# Ver5_1.net
KiCad netlist of a schematic drawn in EAGLE
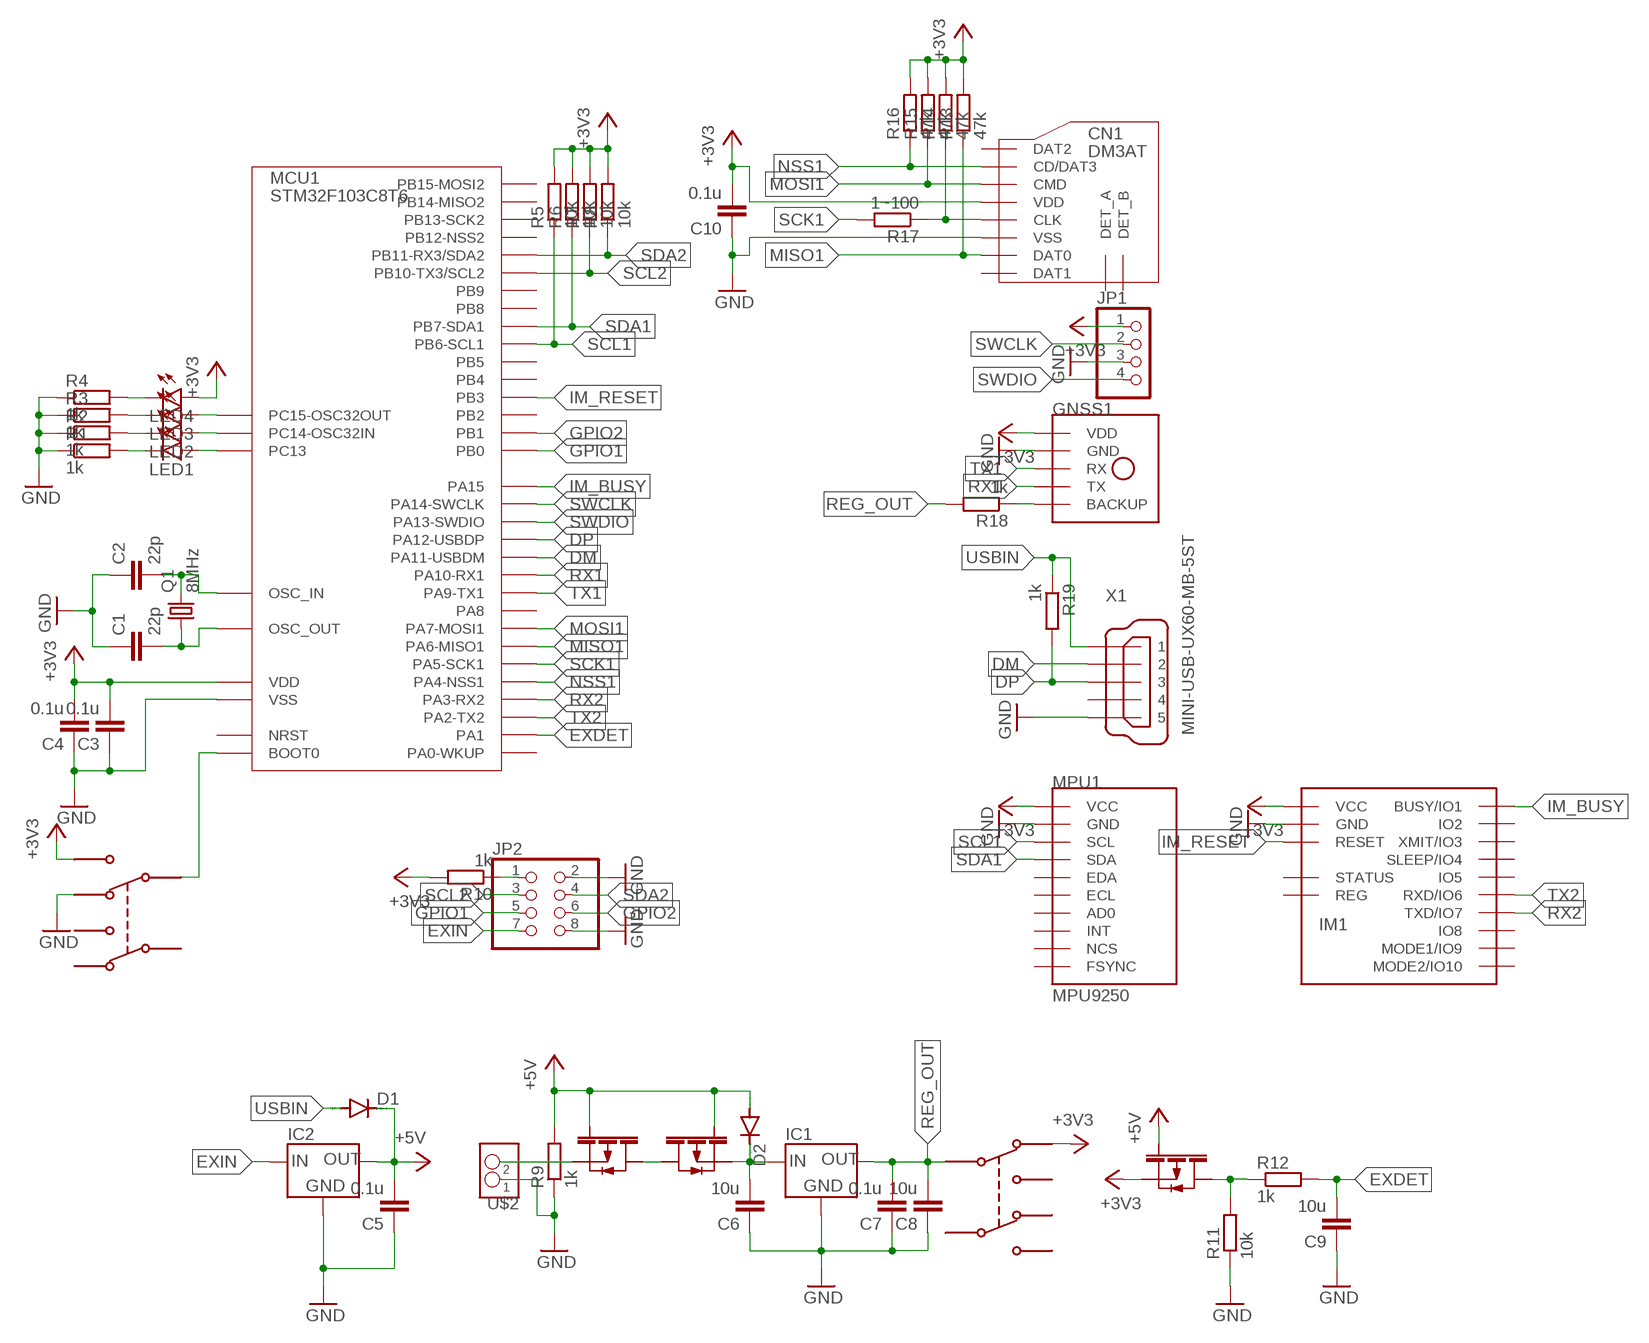
[diagram p0: schematic, sheet 1]

(export (version "E")
  (design (tool "Eeschema 10.0.6"))
  (components
    (comp (ref "C1")
      (value "22p")
      (footprint "eagle-import:C0805")
      (libsource (lib "eagle-import") (part "C-EUC0805"))
    )
    (comp (ref "C2")
      (value "22p")
      (footprint "eagle-import:C0805")
      (libsource (lib "eagle-import") (part "C-EUC0805"))
    )
    (comp (ref "C3")
      (value "0.1u")
      (footprint "eagle-import:C0805")
      (libsource (lib "eagle-import") (part "C-EUC0805"))
    )
    (comp (ref "C4")
      (value "0.1u")
      (footprint "eagle-import:C0805")
      (libsource (lib "eagle-import") (part "C-EUC0805"))
    )
    (comp (ref "C5")
      (value "0.1u")
      (footprint "eagle-import:C0805")
      (libsource (lib "eagle-import") (part "C-EUC0805"))
    )
    (comp (ref "C6")
      (value "10u")
      (footprint "eagle-import:C0805")
      (libsource (lib "eagle-import") (part "C-EUC0805"))
    )
    (comp (ref "C7")
      (value "0.1u")
      (footprint "eagle-import:C0805")
      (libsource (lib "eagle-import") (part "C-EUC0805"))
    )
    (comp (ref "C8")
      (value "10u")
      (footprint "eagle-import:C0805")
      (libsource (lib "eagle-import") (part "C-EUC0805"))
    )
    (comp (ref "C9")
      (value "10u")
      (footprint "eagle-import:C0805")
      (libsource (lib "eagle-import") (part "C-EUC0805"))
    )
    (comp (ref "C10")
      (value "0.1u")
      (footprint "eagle-import:C0805")
      (libsource (lib "eagle-import") (part "C-EUC0805"))
    )
    (comp (ref "CN1")
      (value "DM3AT")
      (footprint "eagle-import:DM3AT")
      (libsource (lib "eagle-import") (part "DM3AT"))
    )
    (comp (ref "D1")
      (value "DIODE-SOD123")
      (footprint "eagle-import:SOD123")
      (libsource (lib "eagle-import") (part "DIODE-SOD123"))
    )
    (comp (ref "D2")
      (value "DIODE-SOD123")
      (footprint "eagle-import:SOD123")
      (libsource (lib "eagle-import") (part "DIODE-SOD123"))
    )
    (comp (ref "FET1")
      (value "PCH")
      (footprint "eagle-import:SOT-23")
      (libsource (lib "eagle-import") (part "PCH"))
    )
    (comp (ref "FET2")
      (value "PCH")
      (footprint "eagle-import:SOT-23")
      (libsource (lib "eagle-import") (part "PCH"))
    )
    (comp (ref "FET3")
      (value "PCH")
      (footprint "eagle-import:SOT-23")
      (libsource (lib "eagle-import") (part "PCH"))
    )
    (comp (ref "GNSS1")
      (value "GYSFDMAXB")
      (footprint "eagle-import:GYSFDMAXB")
      (libsource (lib "eagle-import") (part "GYSFDMAXB"))
    )
    (comp (ref "IC1")
      (value "LT1117-3.3")
      (footprint "eagle-import:SOT-223")
      (libsource (lib "eagle-import") (part "LT1117-3.3"))
    )
    (comp (ref "IC2")
      (value "LT1117-5")
      (footprint "eagle-import:SOT-223")
      (libsource (lib "eagle-import") (part "LT1117-5"))
    )
    (comp (ref "IM1")
      (value "IM920C")
      (footprint "eagle-import:IM920C")
      (libsource (lib "eagle-import") (part "IM920C"))
    )
    (comp (ref "JP1")
      (value "PINHD-1X4/90")
      (footprint "eagle-import:1X04_90")
      (libsource (lib "eagle-import") (part "PINHD-1X4/90"))
    )
    (comp (ref "JP2")
      (value "PINHD-2X4")
      (footprint "eagle-import:2X04")
      (libsource (lib "eagle-import") (part "PINHD-2X4"))
    )
    (comp (ref "LED1")
      (value "LEDSML0805")
      (footprint "eagle-import:SML0805")
      (libsource (lib "eagle-import") (part "LEDSML0805"))
    )
    (comp (ref "LED2")
      (value "LEDSML0805")
      (footprint "eagle-import:SML0805")
      (libsource (lib "eagle-import") (part "LEDSML0805"))
    )
    (comp (ref "LED3")
      (value "LEDSML0805")
      (footprint "eagle-import:SML0805")
      (libsource (lib "eagle-import") (part "LEDSML0805"))
    )
    (comp (ref "LED4")
      (value "LEDSML0805")
      (footprint "eagle-import:SML0805")
      (libsource (lib "eagle-import") (part "LEDSML0805"))
    )
    (comp (ref "MCU1")
      (value "STM32F103C8T6")
      (footprint "eagle-import:LQFP48")
      (libsource (lib "eagle-import") (part "STM32F103C8T6"))
    )
    (comp (ref "MPU1")
      (value "MPU9250")
      (footprint "eagle-import:GY-9250")
      (libsource (lib "eagle-import") (part "MPU9250"))
    )
    (comp (ref "Q1")
      (value "8MHz")
      (footprint "eagle-import:HC49_S")
      (libsource (lib "eagle-import") (part "CRYSTALHC49S"))
    )
    (comp (ref "R1")
      (value "1k")
      (footprint "eagle-import:R0805")
      (libsource (lib "eagle-import") (part "R-EU_R0805"))
    )
    (comp (ref "R2")
      (value "1k")
      (footprint "eagle-import:R0805")
      (libsource (lib "eagle-import") (part "R-EU_R0805"))
    )
    (comp (ref "R3")
      (value "1k")
      (footprint "eagle-import:R0805")
      (libsource (lib "eagle-import") (part "R-EU_R0805"))
    )
    (comp (ref "R4")
      (value "1k")
      (footprint "eagle-import:R0805")
      (libsource (lib "eagle-import") (part "R-EU_R0805"))
    )
    (comp (ref "R5")
      (value "10k")
      (footprint "eagle-import:R0805")
      (libsource (lib "eagle-import") (part "R-EU_R0805"))
    )
    (comp (ref "R6")
      (value "10k")
      (footprint "eagle-import:R0805")
      (libsource (lib "eagle-import") (part "R-EU_R0805"))
    )
    (comp (ref "R7")
      (value "10k")
      (footprint "eagle-import:R0805")
      (libsource (lib "eagle-import") (part "R-EU_R0805"))
    )
    (comp (ref "R8")
      (value "10k")
      (footprint "eagle-import:R0805")
      (libsource (lib "eagle-import") (part "R-EU_R0805"))
    )
    (comp (ref "R9")
      (value "1k")
      (footprint "eagle-import:R0805")
      (libsource (lib "eagle-import") (part "R-EU_R0805"))
    )
    (comp (ref "R10")
      (value "1k")
      (footprint "eagle-import:R0805")
      (libsource (lib "eagle-import") (part "R-EU_R0805"))
    )
    (comp (ref "R11")
      (value "10k")
      (footprint "eagle-import:R0805")
      (libsource (lib "eagle-import") (part "R-EU_R0805"))
    )
    (comp (ref "R12")
      (value "1k")
      (footprint "eagle-import:R0805")
      (libsource (lib "eagle-import") (part "R-EU_R0805"))
    )
    (comp (ref "R13")
      (value "47k")
      (footprint "eagle-import:R0805")
      (libsource (lib "eagle-import") (part "R-EU_R0805"))
    )
    (comp (ref "R14")
      (value "47k")
      (footprint "eagle-import:R0805")
      (libsource (lib "eagle-import") (part "R-EU_R0805"))
    )
    (comp (ref "R15")
      (value "47k")
      (footprint "eagle-import:R0805")
      (libsource (lib "eagle-import") (part "R-EU_R0805"))
    )
    (comp (ref "R16")
      (value "47k")
      (footprint "eagle-import:R0805")
      (libsource (lib "eagle-import") (part "R-EU_R0805"))
    )
    (comp (ref "R17")
      (value "1~100")
      (footprint "eagle-import:R0805")
      (libsource (lib "eagle-import") (part "R-EU_R0805"))
    )
    (comp (ref "R18")
      (value "1k")
      (footprint "eagle-import:R0805")
      (libsource (lib "eagle-import") (part "R-EU_R0805"))
    )
    (comp (ref "R19")
      (value "1k")
      (footprint "eagle-import:R0805")
      (libsource (lib "eagle-import") (part "R-EU_R0805"))
    )
    (comp (ref "U$1")
      (value "MSS22D18")
      (footprint "eagle-import:MSS22D18")
      (libsource (lib "eagle-import") (part "MSS22D18"))
    )
    (comp (ref "U$2")
      (value "S2B-XH-A")
      (footprint "eagle-import:S2B-XH-A")
      (libsource (lib "eagle-import") (part "S2B-XH-A"))
    )
    (comp (ref "U$3")
      (value "MSS22D18")
      (footprint "eagle-import:MSS22D18")
      (libsource (lib "eagle-import") (part "MSS22D18"))
    )
    (comp (ref "X1")
      (value "MINI-USB-UX60-MB-5ST")
      (footprint "eagle-import:UX60-MB-5ST")
      (libsource (lib "eagle-import") (part "MINI-USB-UX60-MB-5ST"))
    )
  )
  (nets
    (net (code "1") (name "+3V3") (class "Default")
      (node (ref "C10") (pin "2") (pinfunction "2_2") (pintype "passive"))
      (node (ref "C3") (pin "2") (pinfunction "2_2") (pintype "passive"))
      (node (ref "C4") (pin "2") (pinfunction "2_2") (pintype "passive"))
      (node (ref "CN1") (pin "VDD") (pinfunction "VDD_VDD") (pintype "bidirectional"))
      (node (ref "FET3") (pin "P$2") (pinfunction "P$2_P$2") (pintype "bidirectional"))
      (node (ref "GNSS1") (pin "P$16") (pinfunction "VDD_P$16") (pintype "bidirectional"))
      (node (ref "IM1") (pin "$P17") (pinfunction "VCC_$P17") (pintype "bidirectional"))
      (node (ref "JP1") (pin "1") (pinfunction "1_1") (pintype "passive"))
      (node (ref "LED4") (pin "A") (pinfunction "A_A") (pintype "passive"))
      (node (ref "MCU1") (pin "1") (pinfunction "VDD_1") (pintype "bidirectional"))
      (node (ref "MCU1") (pin "24") (pinfunction "VDD_24") (pintype "bidirectional"))
      (node (ref "MCU1") (pin "36") (pinfunction "VDD_36") (pintype "bidirectional"))
      (node (ref "MCU1") (pin "48") (pinfunction "VDD_48") (pintype "bidirectional"))
      (node (ref "MCU1") (pin "9") (pinfunction "VDD_9") (pintype "bidirectional"))
      (node (ref "MPU1") (pin "P1") (pinfunction "VCC_P1") (pintype "bidirectional"))
      (node (ref "R10") (pin "2") (pinfunction "2_2") (pintype "passive"))
      (node (ref "R13") (pin "2") (pinfunction "2_2") (pintype "passive"))
      (node (ref "R14") (pin "2") (pinfunction "2_2") (pintype "passive"))
      (node (ref "R15") (pin "2") (pinfunction "2_2") (pintype "passive"))
      (node (ref "R16") (pin "2") (pinfunction "2_2") (pintype "passive"))
      (node (ref "R5") (pin "2") (pinfunction "2_2") (pintype "passive"))
      (node (ref "R6") (pin "2") (pinfunction "2_2") (pintype "passive"))
      (node (ref "R7") (pin "2") (pinfunction "2_2") (pintype "passive"))
      (node (ref "R8") (pin "2") (pinfunction "2_2") (pintype "passive"))
      (node (ref "U$1") (pin "P$0") (pinfunction "P$1_P$0") (pintype "bidirectional"))
      (node (ref "U$3") (pin "P$3") (pinfunction "P$6_P$3") (pintype "bidirectional"))
    )
    (net (code "2") (name "+5V") (class "Default")
      (node (ref "C5") (pin "2") (pinfunction "2_2") (pintype "passive"))
      (node (ref "D1") (pin "C") (pinfunction "C_C") (pintype "passive"))
      (node (ref "D2") (pin "A") (pinfunction "A_A") (pintype "passive"))
      (node (ref "FET1") (pin "P$1") (pinfunction "P$1_P$1") (pintype "bidirectional"))
      (node (ref "FET2") (pin "P$1") (pinfunction "P$1_P$1") (pintype "bidirectional"))
      (node (ref "FET3") (pin "P$1") (pinfunction "P$1_P$1") (pintype "bidirectional"))
      (node (ref "IC2") (pin "2") (pinfunction "OUT_2") (pintype "output"))
      (node (ref "R9") (pin "2") (pinfunction "2_2") (pintype "passive"))
    )
    (net (code "3") (name "DM") (class "Default")
      (node (ref "MCU1") (pin "32") (pinfunction "PA11-USBDM_32") (pintype "bidirectional"))
      (node (ref "X1") (pin "2") (pinfunction "2_2") (pintype "input"))
    )
    (net (code "4") (name "DP") (class "Default")
      (node (ref "MCU1") (pin "33") (pinfunction "PA12-USBDP_33") (pintype "bidirectional"))
      (node (ref "R19") (pin "2") (pinfunction "2_2") (pintype "passive"))
      (node (ref "X1") (pin "3") (pinfunction "3_3") (pintype "input"))
    )
    (net (code "5") (name "EXDET") (class "Default")
      (node (ref "C9") (pin "2") (pinfunction "2_2") (pintype "passive"))
      (node (ref "MCU1") (pin "11") (pinfunction "PA1_11") (pintype "bidirectional"))
      (node (ref "R12") (pin "2") (pinfunction "2_2") (pintype "passive"))
    )
    (net (code "6") (name "EXIN") (class "Default")
      (node (ref "IC2") (pin "3") (pinfunction "IN_3") (pintype "input"))
      (node (ref "JP2") (pin "7") (pinfunction "7_7") (pintype "passive"))
    )
    (net (code "7") (name "GND") (class "Default")
      (node (ref "C1") (pin "1") (pinfunction "1_1") (pintype "passive"))
      (node (ref "C10") (pin "1") (pinfunction "1_1") (pintype "passive"))
      (node (ref "C2") (pin "1") (pinfunction "1_1") (pintype "passive"))
      (node (ref "C3") (pin "1") (pinfunction "1_1") (pintype "passive"))
      (node (ref "C4") (pin "1") (pinfunction "1_1") (pintype "passive"))
      (node (ref "C5") (pin "1") (pinfunction "1_1") (pintype "passive"))
      (node (ref "C6") (pin "1") (pinfunction "1_1") (pintype "passive"))
      (node (ref "C7") (pin "1") (pinfunction "1_1") (pintype "passive"))
      (node (ref "C8") (pin "1") (pinfunction "1_1") (pintype "passive"))
      (node (ref "C9") (pin "1") (pinfunction "1_1") (pintype "passive"))
      (node (ref "CN1") (pin "VSS") (pinfunction "VSS_VSS") (pintype "bidirectional"))
      (node (ref "GNSS1") (pin "P$1") (pinfunction "GND_P$1") (pintype "bidirectional"))
      (node (ref "GNSS1") (pin "P$10") (pinfunction "GND_P$10") (pintype "bidirectional"))
      (node (ref "GNSS1") (pin "P$12") (pinfunction "GND_P$12") (pintype "bidirectional"))
      (node (ref "GNSS1") (pin "P$19") (pinfunction "GND_P$19") (pintype "bidirectional"))
      (node (ref "GNSS1") (pin "P$2") (pinfunction "GND_P$2") (pintype "bidirectional"))
      (node (ref "GNSS1") (pin "P$20") (pinfunction "GND_P$20") (pintype "bidirectional"))
      (node (ref "GNSS1") (pin "P$7") (pinfunction "GND_P$7") (pintype "bidirectional"))
      (node (ref "IC1") (pin "4") (pinfunction "GND_4") (pintype "bidirectional"))
      (node (ref "IC2") (pin "4") (pinfunction "GND_4") (pintype "bidirectional"))
      (node (ref "IM1") (pin "$P18") (pinfunction "GND_$P18") (pintype "bidirectional"))
      (node (ref "JP1") (pin "3") (pinfunction "3_3") (pintype "passive"))
      (node (ref "JP2") (pin "2") (pinfunction "2_2") (pintype "passive"))
      (node (ref "JP2") (pin "8") (pinfunction "8_8") (pintype "passive"))
      (node (ref "MCU1") (pin "23") (pinfunction "VSS_23") (pintype "bidirectional"))
      (node (ref "MCU1") (pin "35") (pinfunction "VSS_35") (pintype "bidirectional"))
      (node (ref "MCU1") (pin "47") (pinfunction "VSS_47") (pintype "bidirectional"))
      (node (ref "MCU1") (pin "8") (pinfunction "VSS_8") (pintype "bidirectional"))
      (node (ref "MPU1") (pin "P2") (pinfunction "GND_P2") (pintype "bidirectional"))
      (node (ref "R1") (pin "1") (pinfunction "1_1") (pintype "passive"))
      (node (ref "R11") (pin "1") (pinfunction "1_1") (pintype "passive"))
      (node (ref "R2") (pin "1") (pinfunction "1_1") (pintype "passive"))
      (node (ref "R3") (pin "1") (pinfunction "1_1") (pintype "passive"))
      (node (ref "R4") (pin "1") (pinfunction "1_1") (pintype "passive"))
      (node (ref "R9") (pin "1") (pinfunction "1_1") (pintype "passive"))
      (node (ref "U$1") (pin "P$2") (pinfunction "P$3_P$2") (pintype "bidirectional"))
      (node (ref "U$2") (pin "P$1") (pinfunction "1_P$1") (pintype "bidirectional"))
      (node (ref "X1") (pin "5") (pinfunction "5_5") (pintype "input"))
    )
    (net (code "8") (name "GPIO1") (class "Default")
      (node (ref "JP2") (pin "5") (pinfunction "5_5") (pintype "passive"))
      (node (ref "MCU1") (pin "18") (pinfunction "PB0_18") (pintype "bidirectional"))
    )
    (net (code "9") (name "GPIO2") (class "Default")
      (node (ref "JP2") (pin "6") (pinfunction "6_6") (pintype "passive"))
      (node (ref "MCU1") (pin "19") (pinfunction "PB1_19") (pintype "bidirectional"))
    )
    (net (code "10") (name "IM_BUSY") (class "Default")
      (node (ref "IM1") (pin "$P1") (pinfunction "BUSY/IO1_$P1") (pintype "bidirectional"))
      (node (ref "MCU1") (pin "38") (pinfunction "PA15_38") (pintype "bidirectional"))
    )
    (net (code "11") (name "IM_RESET") (class "Default")
      (node (ref "IM1") (pin "$P19") (pinfunction "RESET_$P19") (pintype "bidirectional"))
      (node (ref "MCU1") (pin "39") (pinfunction "PB3_39") (pintype "bidirectional"))
    )
    (net (code "12") (name "MISO1") (class "Default")
      (node (ref "CN1") (pin "DAT0") (pinfunction "DAT0_DAT0") (pintype "bidirectional"))
      (node (ref "MCU1") (pin "16") (pinfunction "PA6-MISO1_16") (pintype "bidirectional"))
      (node (ref "R13") (pin "1") (pinfunction "1_1") (pintype "passive"))
    )
    (net (code "13") (name "MOSI1") (class "Default")
      (node (ref "CN1") (pin "CMD") (pinfunction "CMD_CMD") (pintype "bidirectional"))
      (node (ref "MCU1") (pin "17") (pinfunction "PA7-MOSI1_17") (pintype "bidirectional"))
      (node (ref "R15") (pin "1") (pinfunction "1_1") (pintype "passive"))
    )
    (net (code "14") (name "NSS1") (class "Default")
      (node (ref "CN1") (pin "CD/DAT3") (pinfunction "CD/DAT3_CD/DAT3") (pintype "bidirectional"))
      (node (ref "MCU1") (pin "14") (pinfunction "PA4-NSS1_14") (pintype "bidirectional"))
      (node (ref "R16") (pin "1") (pinfunction "1_1") (pintype "passive"))
    )
    (net (code "15") (name "Net-(CN1-PadCLK)") (class "Default")
      (node (ref "CN1") (pin "CLK") (pinfunction "CLK_CLK") (pintype "bidirectional"))
      (node (ref "R14") (pin "1") (pinfunction "1_1") (pintype "passive"))
      (node (ref "R17") (pin "1") (pinfunction "1_1") (pintype "passive"))
    )
    (net (code "16") (name "Net-(FET1-PadP$3)") (class "Default")
      (node (ref "FET1") (pin "P$3") (pinfunction "P$3_P$3") (pintype "bidirectional"))
      (node (ref "FET2") (pin "P$3") (pinfunction "P$3_P$3") (pintype "bidirectional"))
    )
    (net (code "17") (name "Net-(FET3-PadP$3)") (class "Default")
      (node (ref "FET3") (pin "P$3") (pinfunction "P$3_P$3") (pintype "bidirectional"))
      (node (ref "R11") (pin "2") (pinfunction "2_2") (pintype "passive"))
      (node (ref "R12") (pin "1") (pinfunction "1_1") (pintype "passive"))
    )
    (net (code "18") (name "Net-(GNSS1-BACKUP)") (class "Default")
      (node (ref "GNSS1") (pin "P$14") (pinfunction "BACKUP_P$14") (pintype "bidirectional"))
      (node (ref "R18") (pin "1") (pinfunction "1_1") (pintype "passive"))
    )
    (net (code "19") (name "Net-(IC1-IN)") (class "Default")
      (node (ref "C6") (pin "2") (pinfunction "2_2") (pintype "passive"))
      (node (ref "D2") (pin "C") (pinfunction "C_C") (pintype "passive"))
      (node (ref "FET2") (pin "P$2") (pinfunction "P$2_P$2") (pintype "bidirectional"))
      (node (ref "IC1") (pin "3") (pinfunction "IN_3") (pintype "input"))
    )
    (net (code "20") (name "Net-(JP2-Pad1)") (class "Default")
      (node (ref "JP2") (pin "1") (pinfunction "1_1") (pintype "passive"))
      (node (ref "R10") (pin "1") (pinfunction "1_1") (pintype "passive"))
    )
    (net (code "21") (name "Net-(LED1-PadC)") (class "Default")
      (node (ref "LED1") (pin "C") (pinfunction "C_C") (pintype "passive"))
      (node (ref "R1") (pin "2") (pinfunction "2_2") (pintype "passive"))
    )
    (net (code "22") (name "Net-(LED2-PadC)") (class "Default")
      (node (ref "LED2") (pin "C") (pinfunction "C_C") (pintype "passive"))
      (node (ref "R2") (pin "2") (pinfunction "2_2") (pintype "passive"))
    )
    (net (code "23") (name "Net-(LED3-PadC)") (class "Default")
      (node (ref "LED3") (pin "C") (pinfunction "C_C") (pintype "passive"))
      (node (ref "R3") (pin "2") (pinfunction "2_2") (pintype "passive"))
    )
    (net (code "24") (name "Net-(LED4-PadC)") (class "Default")
      (node (ref "LED4") (pin "C") (pinfunction "C_C") (pintype "passive"))
      (node (ref "R4") (pin "2") (pinfunction "2_2") (pintype "passive"))
    )
    (net (code "25") (name "Net-(MCU1-BOOT0)") (class "Default")
      (node (ref "MCU1") (pin "44") (pinfunction "BOOT0_44") (pintype "bidirectional"))
      (node (ref "U$1") (pin "P$1") (pinfunction "P$2_P$1") (pintype "bidirectional"))
    )
    (net (code "26") (name "Net-(MCU1-OSC_IN)") (class "Default")
      (node (ref "C2") (pin "2") (pinfunction "2_2") (pintype "passive"))
      (node (ref "MCU1") (pin "5") (pinfunction "OSC_IN_5") (pintype "bidirectional"))
      (node (ref "Q1") (pin "2") (pinfunction "2_2") (pintype "passive"))
    )
    (net (code "27") (name "Net-(MCU1-OSC_OUT)") (class "Default")
      (node (ref "C1") (pin "2") (pinfunction "2_2") (pintype "passive"))
      (node (ref "MCU1") (pin "6") (pinfunction "OSC_OUT_6") (pintype "bidirectional"))
      (node (ref "Q1") (pin "1") (pinfunction "1_1") (pintype "passive"))
    )
    (net (code "28") (name "Net-(MCU1-PC13)") (class "Default")
      (node (ref "LED1") (pin "A") (pinfunction "A_A") (pintype "passive"))
      (node (ref "MCU1") (pin "2") (pinfunction "PC13_2") (pintype "bidirectional"))
    )
    (net (code "29") (name "Net-(MCU1-PC14-OSC32IN)") (class "Default")
      (node (ref "LED2") (pin "A") (pinfunction "A_A") (pintype "passive"))
      (node (ref "MCU1") (pin "3") (pinfunction "PC14-OSC32IN_3") (pintype "bidirectional"))
    )
    (net (code "30") (name "Net-(MCU1-PC15-OSC32OUT)") (class "Default")
      (node (ref "LED3") (pin "A") (pinfunction "A_A") (pintype "passive"))
      (node (ref "MCU1") (pin "4") (pinfunction "PC15-OSC32OUT_4") (pintype "bidirectional"))
    )
    (net (code "31") (name "Net-(U$2-2)") (class "Default")
      (node (ref "FET1") (pin "P$2") (pinfunction "P$2_P$2") (pintype "bidirectional"))
      (node (ref "U$2") (pin "P$2") (pinfunction "2_P$2") (pintype "bidirectional"))
    )
    (net (code "32") (name "REG_OUT") (class "Default")
      (node (ref "C7") (pin "2") (pinfunction "2_2") (pintype "passive"))
      (node (ref "C8") (pin "2") (pinfunction "2_2") (pintype "passive"))
      (node (ref "IC1") (pin "1") (pinfunction "OUT_1") (pintype "output"))
      (node (ref "IC1") (pin "2") (pinfunction "OUT_2") (pintype "output"))
      (node (ref "R18") (pin "2") (pinfunction "2_2") (pintype "passive"))
      (node (ref "U$3") (pin "P$4") (pinfunction "P$5_P$4") (pintype "bidirectional"))
    )
    (net (code "33") (name "RX1") (class "Default")
      (node (ref "GNSS1") (pin "P$5") (pinfunction "TX_P$5") (pintype "bidirectional"))
      (node (ref "MCU1") (pin "31") (pinfunction "PA10-RX1_31") (pintype "bidirectional"))
    )
    (net (code "34") (name "RX2") (class "Default")
      (node (ref "IM1") (pin "$P7") (pinfunction "TXD/IO7_$P7") (pintype "bidirectional"))
      (node (ref "MCU1") (pin "13") (pinfunction "PA3-RX2_13") (pintype "bidirectional"))
    )
    (net (code "35") (name "SCK1") (class "Default")
      (node (ref "MCU1") (pin "15") (pinfunction "PA5-SCK1_15") (pintype "bidirectional"))
      (node (ref "R17") (pin "2") (pinfunction "2_2") (pintype "passive"))
    )
    (net (code "36") (name "SCL1") (class "Default")
      (node (ref "MCU1") (pin "42") (pinfunction "PB6-SCL1_42") (pintype "bidirectional"))
      (node (ref "MPU1") (pin "P3") (pinfunction "SCL_P3") (pintype "bidirectional"))
      (node (ref "R5") (pin "1") (pinfunction "1_1") (pintype "passive"))
    )
    (net (code "37") (name "SCL2") (class "Default")
      (node (ref "JP2") (pin "3") (pinfunction "3_3") (pintype "passive"))
      (node (ref "MCU1") (pin "21") (pinfunction "PB10-TX3/SCL2_21") (pintype "bidirectional"))
      (node (ref "R7") (pin "1") (pinfunction "1_1") (pintype "passive"))
    )
    (net (code "38") (name "SDA1") (class "Default")
      (node (ref "MCU1") (pin "43") (pinfunction "PB7-SDA1_43") (pintype "bidirectional"))
      (node (ref "MPU1") (pin "P4") (pinfunction "SDA_P4") (pintype "bidirectional"))
      (node (ref "R6") (pin "1") (pinfunction "1_1") (pintype "passive"))
    )
    (net (code "39") (name "SDA2") (class "Default")
      (node (ref "JP2") (pin "4") (pinfunction "4_4") (pintype "passive"))
      (node (ref "MCU1") (pin "22") (pinfunction "PB11-RX3/SDA2_22") (pintype "bidirectional"))
      (node (ref "R8") (pin "1") (pinfunction "1_1") (pintype "passive"))
    )
    (net (code "40") (name "SWCLK") (class "Default")
      (node (ref "JP1") (pin "2") (pinfunction "2_2") (pintype "passive"))
      (node (ref "MCU1") (pin "37") (pinfunction "PA14-SWCLK_37") (pintype "bidirectional"))
    )
    (net (code "41") (name "SWDIO") (class "Default")
      (node (ref "JP1") (pin "4") (pinfunction "4_4") (pintype "passive"))
      (node (ref "MCU1") (pin "34") (pinfunction "PA13-SWDIO_34") (pintype "bidirectional"))
    )
    (net (code "42") (name "TX1") (class "Default")
      (node (ref "GNSS1") (pin "P$3") (pinfunction "RX_P$3") (pintype "bidirectional"))
      (node (ref "MCU1") (pin "30") (pinfunction "PA9-TX1_30") (pintype "bidirectional"))
    )
    (net (code "43") (name "TX2") (class "Default")
      (node (ref "IM1") (pin "$P6") (pinfunction "RXD/IO6_$P6") (pintype "bidirectional"))
      (node (ref "MCU1") (pin "12") (pinfunction "PA2-TX2_12") (pintype "bidirectional"))
    )
    (net (code "44") (name "USBIN") (class "Default")
      (node (ref "D1") (pin "A") (pinfunction "A_A") (pintype "passive"))
      (node (ref "R19") (pin "1") (pinfunction "1_1") (pintype "passive"))
      (node (ref "X1") (pin "1") (pinfunction "1_1") (pintype "input"))
    )
    (net (code "45") (name "unconnected-(CN1-PadDAT1)") (class "Default")
      (node (ref "CN1") (pin "DAT1") (pinfunction "DAT1_DAT1") (pintype "bidirectional"))
    )
    (net (code "46") (name "unconnected-(CN1-PadDAT2)") (class "Default")
      (node (ref "CN1") (pin "DAT2") (pinfunction "DAT2_DAT2") (pintype "bidirectional"))
    )
    (net (code "47") (name "unconnected-(CN1-PadDET_A)") (class "Default")
      (node (ref "CN1") (pin "DET_A") (pinfunction "DET_A_DET_A") (pintype "bidirectional"))
    )
    (net (code "48") (name "unconnected-(CN1-PadDET_B)") (class "Default")
      (node (ref "CN1") (pin "DET_B") (pinfunction "DET_B_DET_B") (pintype "bidirectional"))
    )
    (net (code "49") (name "unconnected-(IM1-IO2-Pad$P2)") (class "Default")
      (node (ref "IM1") (pin "$P2") (pinfunction "IO2_$P2") (pintype "bidirectional"))
    )
    (net (code "50") (name "unconnected-(IM1-IO5-Pad$P5)") (class "Default")
      (node (ref "IM1") (pin "$P5") (pinfunction "IO5_$P5") (pintype "bidirectional"))
    )
    (net (code "51") (name "unconnected-(IM1-IO8-Pad$P8)") (class "Default")
      (node (ref "IM1") (pin "$P8") (pinfunction "IO8_$P8") (pintype "bidirectional"))
    )
    (net (code "52") (name "unconnected-(IM1-MODE1{slash}IO9-Pad$P9)") (class "Default")
      (node (ref "IM1") (pin "$P9") (pinfunction "MODE1/IO9_$P9") (pintype "bidirectional"))
    )
    (net (code "53") (name "unconnected-(IM1-MODE2{slash}IO10-Pad$P10)") (class "Default")
      (node (ref "IM1") (pin "$P10") (pinfunction "MODE2/IO10_$P10") (pintype "bidirectional"))
    )
    (net (code "54") (name "unconnected-(IM1-REG-Pad$P16)") (class "Default")
      (node (ref "IM1") (pin "$P16") (pinfunction "REG_$P16") (pintype "bidirectional"))
    )
    (net (code "55") (name "unconnected-(IM1-SLEEP{slash}IO4-Pad$P4)") (class "Default")
      (node (ref "IM1") (pin "$P4") (pinfunction "SLEEP/IO4_$P4") (pintype "bidirectional"))
    )
    (net (code "56") (name "unconnected-(IM1-STATUS-Pad$P15)") (class "Default")
      (node (ref "IM1") (pin "$P15") (pinfunction "STATUS_$P15") (pintype "bidirectional"))
    )
    (net (code "57") (name "unconnected-(IM1-XMIT{slash}IO3-Pad$P3)") (class "Default")
      (node (ref "IM1") (pin "$P3") (pinfunction "XMIT/IO3_$P3") (pintype "bidirectional"))
    )
    (net (code "58") (name "unconnected-(MCU1-NRST-Pad7)") (class "Default")
      (node (ref "MCU1") (pin "7") (pinfunction "NRST_7") (pintype "bidirectional"))
    )
    (net (code "59") (name "unconnected-(MCU1-PA0-WKUP-Pad10)") (class "Default")
      (node (ref "MCU1") (pin "10") (pinfunction "PA0-WKUP_10") (pintype "bidirectional"))
    )
    (net (code "60") (name "unconnected-(MCU1-PA8-Pad29)") (class "Default")
      (node (ref "MCU1") (pin "29") (pinfunction "PA8_29") (pintype "bidirectional"))
    )
    (net (code "61") (name "unconnected-(MCU1-PB2-Pad20)") (class "Default")
      (node (ref "MCU1") (pin "20") (pinfunction "PB2_20") (pintype "bidirectional"))
    )
    (net (code "62") (name "unconnected-(MCU1-PB4-Pad40)") (class "Default")
      (node (ref "MCU1") (pin "40") (pinfunction "PB4_40") (pintype "bidirectional"))
    )
    (net (code "63") (name "unconnected-(MCU1-PB5-Pad41)") (class "Default")
      (node (ref "MCU1") (pin "41") (pinfunction "PB5_41") (pintype "bidirectional"))
    )
    (net (code "64") (name "unconnected-(MCU1-PB8-Pad45)") (class "Default")
      (node (ref "MCU1") (pin "45") (pinfunction "PB8_45") (pintype "bidirectional"))
    )
    (net (code "65") (name "unconnected-(MCU1-PB9-Pad46)") (class "Default")
      (node (ref "MCU1") (pin "46") (pinfunction "PB9_46") (pintype "bidirectional"))
    )
    (net (code "66") (name "unconnected-(MCU1-PB12-NSS2-Pad25)") (class "Default")
      (node (ref "MCU1") (pin "25") (pinfunction "PB12-NSS2_25") (pintype "bidirectional"))
    )
    (net (code "67") (name "unconnected-(MCU1-PB13-SCK2-Pad26)") (class "Default")
      (node (ref "MCU1") (pin "26") (pinfunction "PB13-SCK2_26") (pintype "bidirectional"))
    )
    (net (code "68") (name "unconnected-(MCU1-PB14-MISO2-Pad27)") (class "Default")
      (node (ref "MCU1") (pin "27") (pinfunction "PB14-MISO2_27") (pintype "bidirectional"))
    )
    (net (code "69") (name "unconnected-(MCU1-PB15-MOSI2-Pad28)") (class "Default")
      (node (ref "MCU1") (pin "28") (pinfunction "PB15-MOSI2_28") (pintype "bidirectional"))
    )
    (net (code "70") (name "unconnected-(MPU1-AD0-PadP7)") (class "Default")
      (node (ref "MPU1") (pin "P7") (pinfunction "AD0_P7") (pintype "bidirectional"))
    )
    (net (code "71") (name "unconnected-(MPU1-ECL-PadP6)") (class "Default")
      (node (ref "MPU1") (pin "P6") (pinfunction "ECL_P6") (pintype "bidirectional"))
    )
    (net (code "72") (name "unconnected-(MPU1-EDA-PadP5)") (class "Default")
      (node (ref "MPU1") (pin "P5") (pinfunction "EDA_P5") (pintype "bidirectional"))
    )
    (net (code "73") (name "unconnected-(MPU1-FSYNC-PadP10)") (class "Default")
      (node (ref "MPU1") (pin "P10") (pinfunction "FSYNC_P10") (pintype "bidirectional"))
    )
    (net (code "74") (name "unconnected-(MPU1-INT-PadP8)") (class "Default")
      (node (ref "MPU1") (pin "P8") (pinfunction "INT_P8") (pintype "bidirectional"))
    )
    (net (code "75") (name "unconnected-(MPU1-NCS-PadP9)") (class "Default")
      (node (ref "MPU1") (pin "P9") (pinfunction "NCS_P9") (pintype "bidirectional"))
    )
    (net (code "76") (name "unconnected-(U$1-P$4-PadP$5)") (class "Default")
      (node (ref "U$1") (pin "P$5") (pinfunction "P$4_P$5") (pintype "bidirectional"))
    )
    (net (code "77") (name "unconnected-(U$1-P$5-PadP$4)") (class "Default")
      (node (ref "U$1") (pin "P$4") (pinfunction "P$5_P$4") (pintype "bidirectional"))
    )
    (net (code "78") (name "unconnected-(U$1-P$6-PadP$3)") (class "Default")
      (node (ref "U$1") (pin "P$3") (pinfunction "P$6_P$3") (pintype "bidirectional"))
    )
    (net (code "79") (name "unconnected-(U$3-P$1-PadP$0)") (class "Default")
      (node (ref "U$3") (pin "P$0") (pinfunction "P$1_P$0") (pintype "bidirectional"))
    )
    (net (code "80") (name "unconnected-(U$3-P$2-PadP$1)") (class "Default")
      (node (ref "U$3") (pin "P$1") (pinfunction "P$2_P$1") (pintype "bidirectional"))
    )
    (net (code "81") (name "unconnected-(U$3-P$3-PadP$2)") (class "Default")
      (node (ref "U$3") (pin "P$2") (pinfunction "P$3_P$2") (pintype "bidirectional"))
    )
    (net (code "82") (name "unconnected-(U$3-P$4-PadP$5)") (class "Default")
      (node (ref "U$3") (pin "P$5") (pinfunction "P$4_P$5") (pintype "bidirectional"))
    )
    (net (code "83") (name "unconnected-(X1-Pad4)") (class "Default")
      (node (ref "X1") (pin "4") (pinfunction "4_4") (pintype "input"))
    )
  )
)
